# labwiz-module_pH.net
KiCad netlist of a schematic drawn in EAGLE
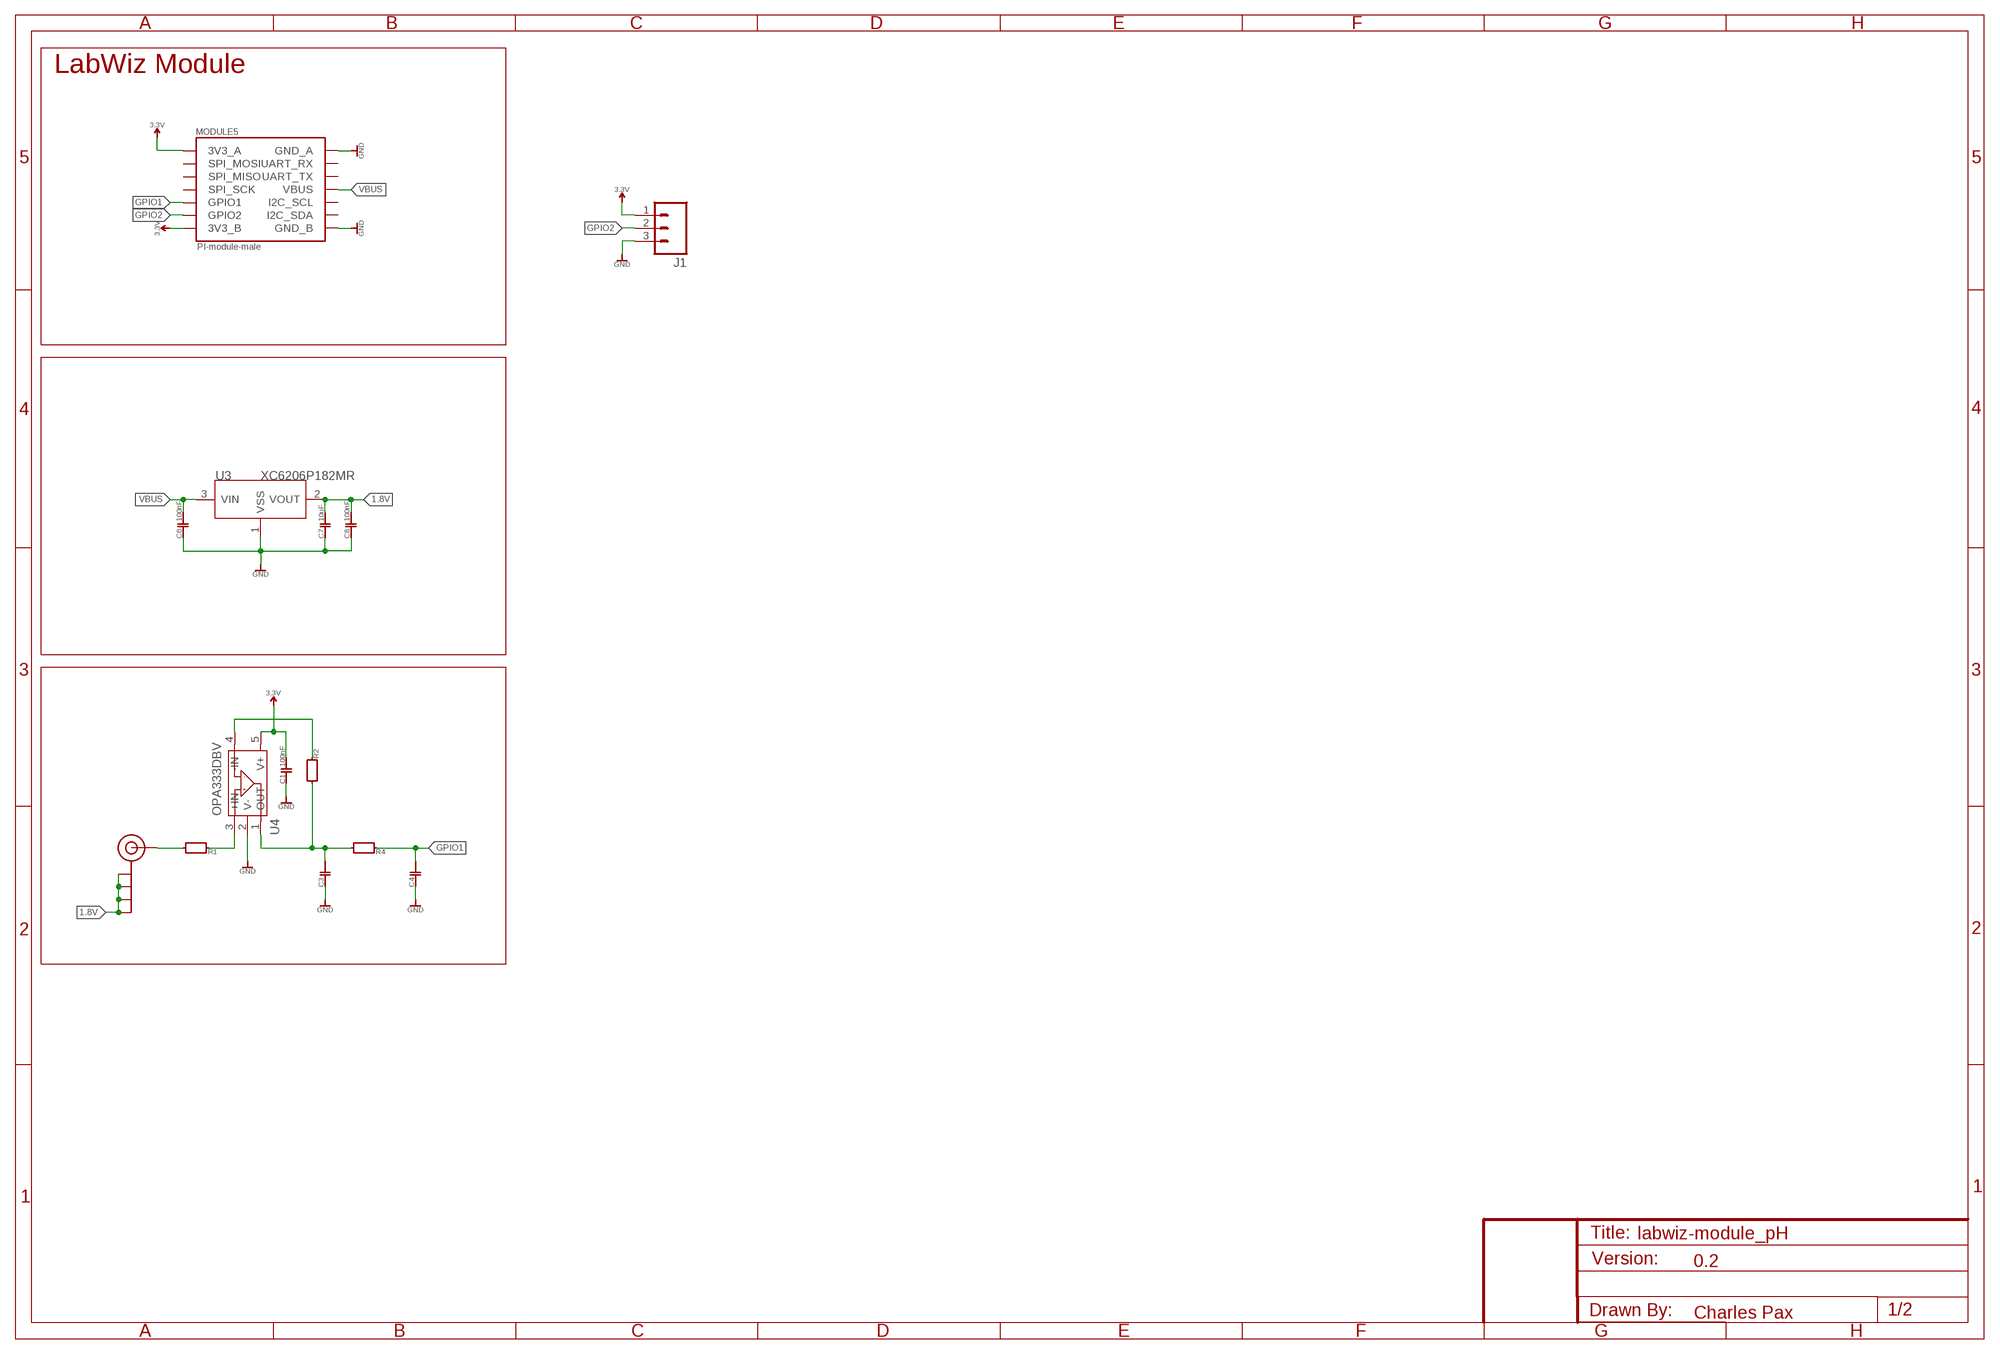
[diagram p0: schematic, sheet 1]

(export (version "E")
  (design (tool "Eeschema 10.0.6"))
  (components
    (comp (ref "C1")
      (value "100nF")
      (footprint "eagle-import:0603")
      (libsource (lib "eagle-import") (part "CAPACITOR_FIXED_0603_100NF"))
    )
    (comp (ref "C3")
      (value "CAPACITOR_FIXED_0603")
      (footprint "eagle-import:0603")
      (libsource (lib "eagle-import") (part "CAPACITOR_FIXED_0603"))
    )
    (comp (ref "C4")
      (value "CAPACITOR_FIXED_0603")
      (footprint "eagle-import:0603")
      (libsource (lib "eagle-import") (part "CAPACITOR_FIXED_0603"))
    )
    (comp (ref "C6")
      (value "100nF")
      (footprint "eagle-import:0603")
      (libsource (lib "eagle-import") (part "CAPACITOR_FIXED_0603_100NF"))
    )
    (comp (ref "C7")
      (value "10uF")
      (footprint "eagle-import:0603")
      (libsource (lib "eagle-import") (part "CAPACITOR_FIXED_0603_10UF"))
    )
    (comp (ref "C8")
      (value "100nF")
      (footprint "eagle-import:0603")
      (libsource (lib "eagle-import") (part "CAPACITOR_FIXED_0603_100NF"))
    )
    (comp (ref "J$1")
      (value "SMA_EDGE")
      (footprint "eagle-import:SMA-EDGE")
      (libsource (lib "eagle-import") (part "SMA_EDGE"))
    )
    (comp (ref "J1")
      (value "M03LOCK_LONGPADS")
      (footprint "eagle-import:1X03_LOCK_LONGPADS")
      (libsource (lib "eagle-import") (part "M03LOCK_LONGPADS"))
    )
    (comp (ref "MODULE5")
      (value "PI-module-male")
      (footprint "eagle-import:M07X2_2MM_EDGE")
      (fields (field (name "MF") "Pax Instruments") (field (name "MPN") "PIxxxx"))
      (libsource (lib "eagle-import") (part "PAX_MODULE_EDGE_MALE_MODULE"))
    )
    (comp (ref "R1")
      (value "RESISTOR_FIXED_0603")
      (footprint "eagle-import:0603")
      (libsource (lib "eagle-import") (part "RESISTOR_FIXED_0603"))
    )
    (comp (ref "R2")
      (value "RESISTOR_FIXED_0603")
      (footprint "eagle-import:0603")
      (libsource (lib "eagle-import") (part "RESISTOR_FIXED_0603"))
    )
    (comp (ref "R4")
      (value "RESISTOR_FIXED_0603")
      (footprint "eagle-import:0603")
      (libsource (lib "eagle-import") (part "RESISTOR_FIXED_0603"))
    )
    (comp (ref "U3")
      (value "XC6206P182MR")
      (footprint "eagle-import:SOT23")
      (libsource (lib "eagle-import") (part "XC6206MR"))
    )
    (comp (ref "U4")
      (value "OPA333DBV")
      (footprint "eagle-import:SOT23-5")
      (libsource (lib "eagle-import") (part "OPA333DBV"))
    )
  )
  (nets
    (net (code "1") (name "1.8V") (class "Default")
      (node (ref "C7") (pin "2") (pinfunction "2_2") (pintype "passive"))
      (node (ref "C8") (pin "2") (pinfunction "2_2") (pintype "passive"))
      (node (ref "J$1") (pin "GND@0") (pinfunction "GND_GND@0") (pintype "bidirectional"))
      (node (ref "J$1") (pin "GND@1") (pinfunction "GND_GND@1") (pintype "bidirectional"))
      (node (ref "J$1") (pin "GND@2") (pinfunction "GND_GND@2") (pintype "bidirectional"))
      (node (ref "J$1") (pin "GND@3") (pinfunction "GND_GND@3") (pintype "bidirectional"))
      (node (ref "U3") (pin "2") (pinfunction "VOUT_2") (pintype "output"))
    )
    (net (code "2") (name "3.3V") (class "Default")
      (node (ref "C1") (pin "2") (pinfunction "2_2") (pintype "passive"))
      (node (ref "J1") (pin "1") (pinfunction "1_1") (pintype "passive"))
      (node (ref "MODULE5") (pin "P$1") (pinfunction "3V3_B_P$1") (pintype "bidirectional"))
      (node (ref "MODULE5") (pin "P$13") (pinfunction "3V3_A_P$13") (pintype "power_in"))
      (node (ref "U4") (pin "5") (pinfunction "V+_5") (pintype "bidirectional"))
    )
    (net (code "3") (name "GND") (class "Default")
      (node (ref "C1") (pin "1") (pinfunction "1_1") (pintype "passive"))
      (node (ref "C3") (pin "1") (pinfunction "1_1") (pintype "passive"))
      (node (ref "C4") (pin "1") (pinfunction "1_1") (pintype "passive"))
      (node (ref "C6") (pin "1") (pinfunction "1_1") (pintype "passive"))
      (node (ref "C7") (pin "1") (pinfunction "1_1") (pintype "passive"))
      (node (ref "C8") (pin "1") (pinfunction "1_1") (pintype "passive"))
      (node (ref "J1") (pin "3") (pinfunction "3_3") (pintype "passive"))
      (node (ref "MODULE5") (pin "P$14") (pinfunction "GND_A_P$14") (pintype "power_in"))
      (node (ref "MODULE5") (pin "P$2") (pinfunction "GND_B_P$2") (pintype "bidirectional"))
      (node (ref "U3") (pin "1") (pinfunction "VSS_1") (pintype "power_in"))
      (node (ref "U4") (pin "2") (pinfunction "V-_2") (pintype "bidirectional"))
    )
    (net (code "4") (name "GPIO1") (class "Default")
      (node (ref "C4") (pin "2") (pinfunction "2_2") (pintype "passive"))
      (node (ref "MODULE5") (pin "P$5") (pinfunction "GPIO1_P$5") (pintype "bidirectional"))
      (node (ref "R4") (pin "2") (pinfunction "2_2") (pintype "passive"))
    )
    (net (code "5") (name "GPIO2") (class "Default")
      (node (ref "J1") (pin "2") (pinfunction "2_2") (pintype "passive"))
      (node (ref "MODULE5") (pin "P$3") (pinfunction "GPIO2_P$3") (pintype "bidirectional"))
    )
    (net (code "6") (name "Net-(J$1-SIGNAL)") (class "Default")
      (node (ref "J$1") (pin "SIG") (pinfunction "SIGNAL_SIG") (pintype "bidirectional"))
      (node (ref "R1") (pin "1") (pinfunction "1_1") (pintype "passive"))
    )
    (net (code "7") (name "Net-(U4-+IN)") (class "Default")
      (node (ref "R1") (pin "2") (pinfunction "2_2") (pintype "passive"))
      (node (ref "U4") (pin "3") (pinfunction "+IN_3") (pintype "bidirectional"))
    )
    (net (code "8") (name "Net-(U4--IN)") (class "Default")
      (node (ref "R2") (pin "2") (pinfunction "2_2") (pintype "passive"))
      (node (ref "U4") (pin "4") (pinfunction "-IN_4") (pintype "bidirectional"))
    )
    (net (code "9") (name "Net-(U4-OUT)") (class "Default")
      (node (ref "C3") (pin "2") (pinfunction "2_2") (pintype "passive"))
      (node (ref "R2") (pin "1") (pinfunction "1_1") (pintype "passive"))
      (node (ref "R4") (pin "1") (pinfunction "1_1") (pintype "passive"))
      (node (ref "U4") (pin "1") (pinfunction "OUT_1") (pintype "bidirectional"))
    )
    (net (code "10") (name "VBUS") (class "Default")
      (node (ref "C6") (pin "2") (pinfunction "2_2") (pintype "passive"))
      (node (ref "MODULE5") (pin "P$8") (pinfunction "VBUS_P$8") (pintype "bidirectional"))
      (node (ref "U3") (pin "3") (pinfunction "VIN_3") (pintype "input"))
    )
    (net (code "11") (name "unconnected-(MODULE5-I2C_SCL-PadP$6)") (class "Default")
      (node (ref "MODULE5") (pin "P$6") (pinfunction "I2C_SCL_P$6") (pintype "bidirectional"))
    )
    (net (code "12") (name "unconnected-(MODULE5-I2C_SDA-PadP$4)") (class "Default")
      (node (ref "MODULE5") (pin "P$4") (pinfunction "I2C_SDA_P$4") (pintype "bidirectional"))
    )
    (net (code "13") (name "unconnected-(MODULE5-SPI_MISO-PadP$9)") (class "Default")
      (node (ref "MODULE5") (pin "P$9") (pinfunction "SPI_MISO_P$9") (pintype "bidirectional"))
    )
    (net (code "14") (name "unconnected-(MODULE5-SPI_MOSI-PadP$11)") (class "Default")
      (node (ref "MODULE5") (pin "P$11") (pinfunction "SPI_MOSI_P$11") (pintype "bidirectional"))
    )
    (net (code "15") (name "unconnected-(MODULE5-SPI_SCK-PadP$7)") (class "Default")
      (node (ref "MODULE5") (pin "P$7") (pinfunction "SPI_SCK_P$7") (pintype "bidirectional"))
    )
    (net (code "16") (name "unconnected-(MODULE5-UART_RX-PadP$12)") (class "Default")
      (node (ref "MODULE5") (pin "P$12") (pinfunction "UART_RX_P$12") (pintype "bidirectional"))
    )
    (net (code "17") (name "unconnected-(MODULE5-UART_TX-PadP$10)") (class "Default")
      (node (ref "MODULE5") (pin "P$10") (pinfunction "UART_TX_P$10") (pintype "bidirectional"))
    )
  )
)
